# untitled.net
KiCad netlist of a schematic drawn in EAGLE
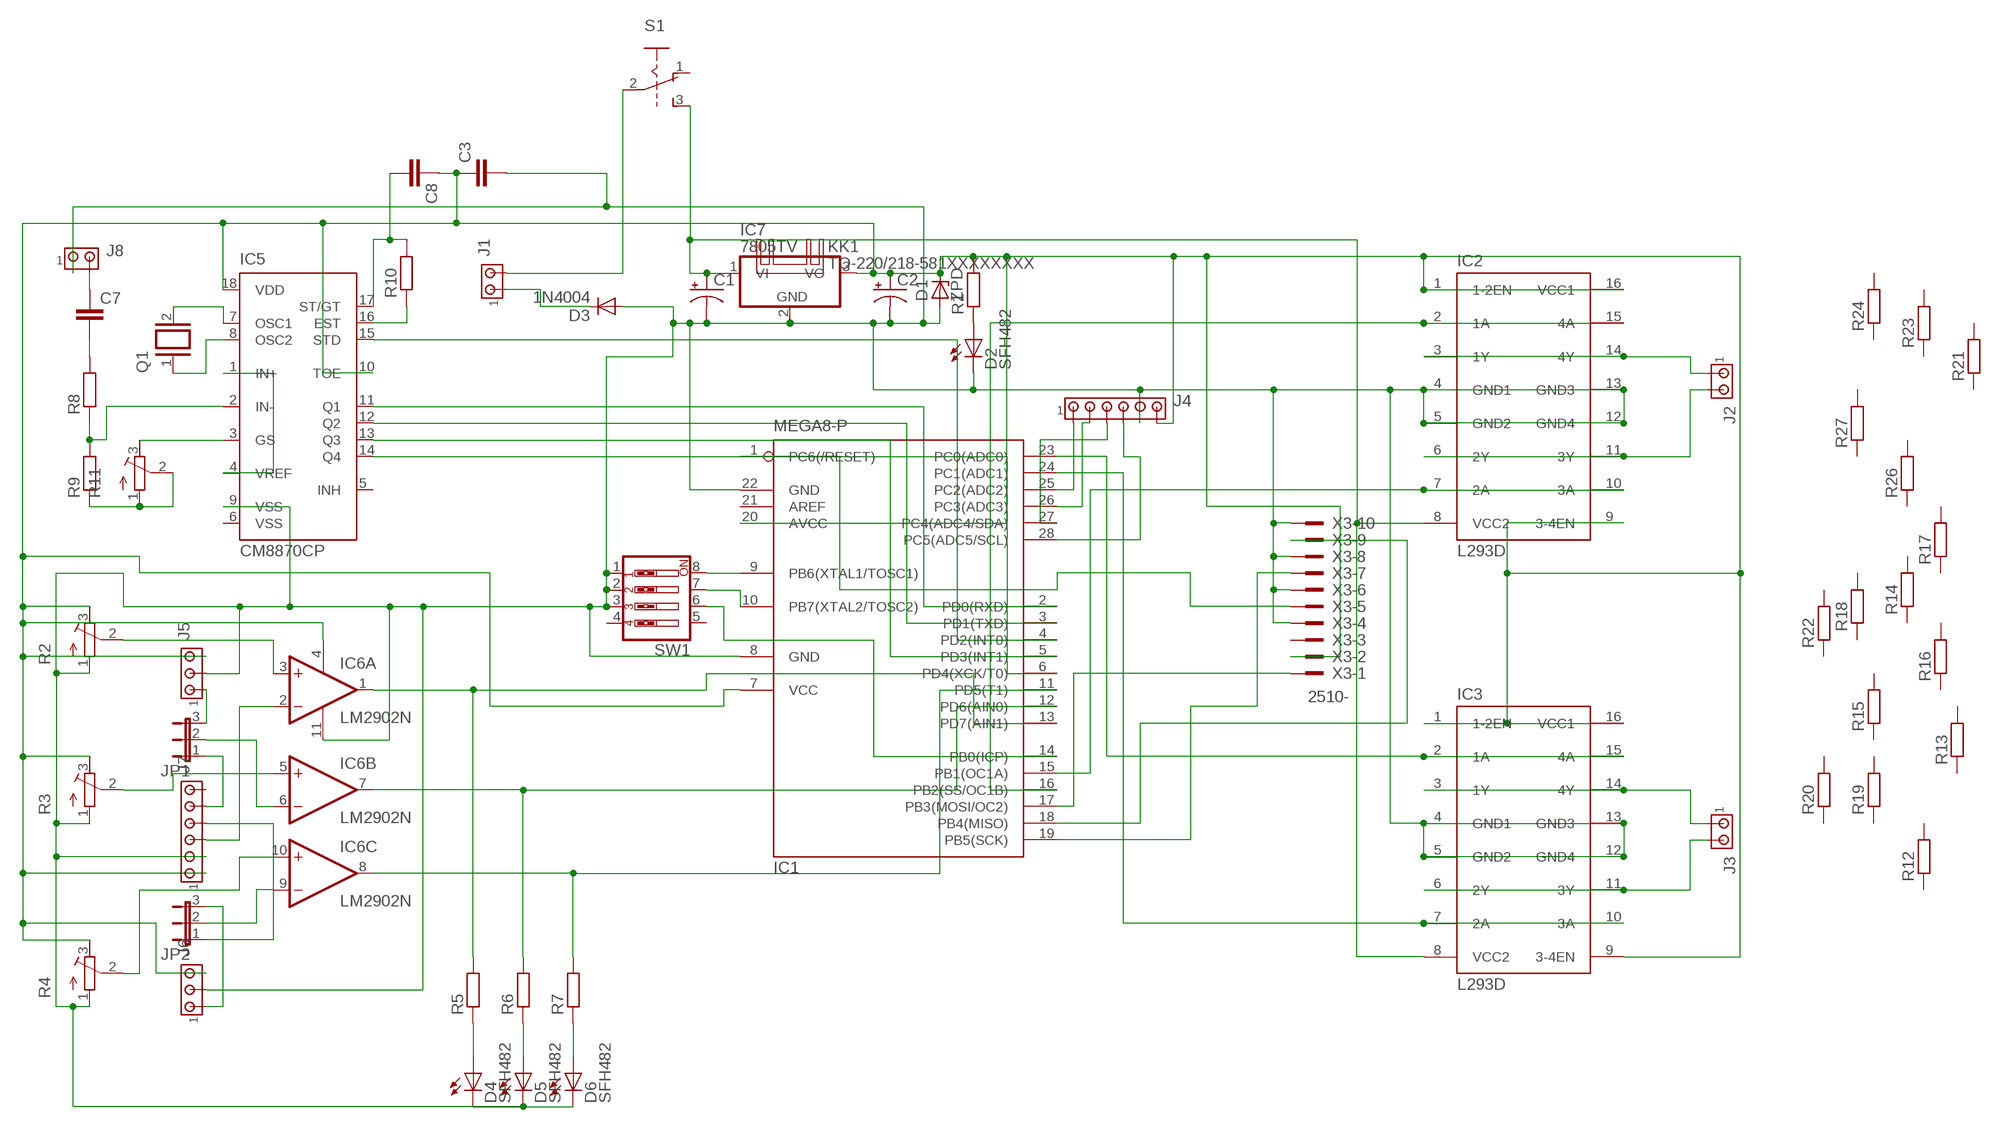
[diagram p0: schematic, sheet 1]

(export (version "E")
  (design (tool "Eeschema 10.0.6"))
  (components
    (comp (ref "C1")
      (value "CPOL-USE5-10.5")
      (footprint "eagle-import:E5-10,5")
      (libsource (lib "eagle-import") (part "CPOL-USE5-10.5"))
    )
    (comp (ref "C2")
      (value "CPOL-USE5-10.5")
      (footprint "eagle-import:E5-10,5")
      (libsource (lib "eagle-import") (part "CPOL-USE5-10.5"))
    )
    (comp (ref "C3")
      (value "C2.5/2")
      (footprint "eagle-import:C2.5-2")
      (libsource (lib "eagle-import") (part "C2.5/2"))
    )
    (comp (ref "C7")
      (value "C5/2.5")
      (footprint "eagle-import:C5B2.5")
      (libsource (lib "eagle-import") (part "C5/2.5"))
    )
    (comp (ref "C8")
      (value "C5/2.5")
      (footprint "eagle-import:C5B2.5")
      (libsource (lib "eagle-import") (part "C5/2.5"))
    )
    (comp (ref "D1")
      (value "ZPD")
      (footprint "eagle-import:DO35Z10")
      (libsource (lib "eagle-import") (part "ZPD"))
    )
    (comp (ref "D2")
      (value "SFH482")
      (footprint "eagle-import:SFH482")
      (libsource (lib "eagle-import") (part "SFH482"))
    )
    (comp (ref "D3")
      (value "1N4004")
      (footprint "eagle-import:DO41-10")
      (libsource (lib "eagle-import") (part "1N4004"))
    )
    (comp (ref "D4")
      (value "SFH482")
      (footprint "eagle-import:SFH482")
      (libsource (lib "eagle-import") (part "SFH482"))
    )
    (comp (ref "D5")
      (value "SFH482")
      (footprint "eagle-import:SFH482")
      (libsource (lib "eagle-import") (part "SFH482"))
    )
    (comp (ref "D6")
      (value "SFH482")
      (footprint "eagle-import:SFH482")
      (libsource (lib "eagle-import") (part "SFH482"))
    )
    (comp (ref "IC1")
      (value "MEGA8-P")
      (footprint "eagle-import:DIL28-3")
      (libsource (lib "eagle-import") (part "MEGA8-P"))
    )
    (comp (ref "IC2")
      (value "L293D")
      (footprint "eagle-import:DIL16")
      (libsource (lib "eagle-import") (part "L293D"))
    )
    (comp (ref "IC3")
      (value "L293D")
      (footprint "eagle-import:DIL16")
      (libsource (lib "eagle-import") (part "L293D"))
    )
    (comp (ref "IC5")
      (value "CM8870CP")
      (footprint "eagle-import:DIL18")
      (libsource (lib "eagle-import") (part "CM8870CP"))
    )
    (comp (ref "IC6")
      (value "LM2902N")
      (footprint "eagle-import:DIL14")
      (libsource (lib "eagle-import") (part "LM2902N"))
    )
    (comp (ref "IC7")
      (value "7805TV")
      (footprint "eagle-import:TO220V")
      (libsource (lib "eagle-import") (part "78TV05"))
    )
    (comp (ref "J1")
      (value "MTA02-100")
      (footprint "eagle-import:10X02MTA")
      (libsource (lib "eagle-import") (part "MTA02-100"))
    )
    (comp (ref "J2")
      (value "MTA02-156")
      (footprint "eagle-import:1X2MTA")
      (libsource (lib "eagle-import") (part "MTA02-156"))
    )
    (comp (ref "J3")
      (value "MTA02-156")
      (footprint "eagle-import:1X2MTA")
      (libsource (lib "eagle-import") (part "MTA02-156"))
    )
    (comp (ref "J4")
      (value "MTA06-100")
      (footprint "eagle-import:10X06MTA")
      (libsource (lib "eagle-import") (part "MTA06-100"))
    )
    (comp (ref "J5")
      (value "MTA03-100")
      (footprint "eagle-import:10X03MTA")
      (libsource (lib "eagle-import") (part "MTA03-100"))
    )
    (comp (ref "J6")
      (value "MTA03-100")
      (footprint "eagle-import:10X03MTA")
      (libsource (lib "eagle-import") (part "MTA03-100"))
    )
    (comp (ref "J7")
      (value "MTA06-100")
      (footprint "eagle-import:10X06MTA")
      (libsource (lib "eagle-import") (part "MTA06-100"))
    )
    (comp (ref "J8")
      (value "MTA02-100")
      (footprint "eagle-import:10X02MTA")
      (libsource (lib "eagle-import") (part "MTA02-100"))
    )
    (comp (ref "JP1")
      (value "JP2E")
      (footprint "eagle-import:JP2")
      (libsource (lib "eagle-import") (part "JP2E"))
    )
    (comp (ref "JP2")
      (value "JP2E")
      (footprint "eagle-import:JP2")
      (libsource (lib "eagle-import") (part "JP2E"))
    )
    (comp (ref "KK1")
      (value "TO-220/218-581XXXXXXXX")
      (footprint "eagle-import:581XXXXXXXX")
      (libsource (lib "eagle-import") (part "TO-220/218-581XXXXXXXX"))
    )
    (comp (ref "Q1")
      (value "XTAL/S")
      (footprint "eagle-import:QS")
      (libsource (lib "eagle-import") (part "XTAL/S"))
    )
    (comp (ref "R1")
      (value "R-EU_0207/10")
      (footprint "eagle-import:0207_10")
      (libsource (lib "eagle-import") (part "resistor_R-EU_0207/10"))
    )
    (comp (ref "R2")
      (value "R-TRIMM3296W")
      (footprint "eagle-import:RTRIM3296W")
      (libsource (lib "eagle-import") (part "R-TRIMM3296W"))
    )
    (comp (ref "R3")
      (value "R-TRIMM3296W")
      (footprint "eagle-import:RTRIM3296W")
      (libsource (lib "eagle-import") (part "R-TRIMM3296W"))
    )
    (comp (ref "R4")
      (value "R-TRIMM3296W")
      (footprint "eagle-import:RTRIM3296W")
      (libsource (lib "eagle-import") (part "R-TRIMM3296W"))
    )
    (comp (ref "R5")
      (value "R-EU_0207/10")
      (footprint "eagle-import:0207_10")
      (libsource (lib "eagle-import") (part "resistor_R-EU_0207/10"))
    )
    (comp (ref "R6")
      (value "R-EU_0207/10")
      (footprint "eagle-import:0207_10")
      (libsource (lib "eagle-import") (part "resistor_R-EU_0207/10"))
    )
    (comp (ref "R7")
      (value "R-EU_0207/10")
      (footprint "eagle-import:0207_10")
      (libsource (lib "eagle-import") (part "resistor_R-EU_0207/10"))
    )
    (comp (ref "R8")
      (value "R-EU_0207/10")
      (footprint "eagle-import:0207_10")
      (libsource (lib "eagle-import") (part "R-EU_0207/10"))
    )
    (comp (ref "R9")
      (value "R-EU_0207/10")
      (footprint "eagle-import:0207_10")
      (libsource (lib "eagle-import") (part "R-EU_0207/10"))
    )
    (comp (ref "R10")
      (value "R-EU_0207/10")
      (footprint "eagle-import:0207_10")
      (libsource (lib "eagle-import") (part "R-EU_0207/10"))
    )
    (comp (ref "R11")
      (value "R-TRIMM3296W")
      (footprint "eagle-import:RTRIM3296W")
      (libsource (lib "eagle-import") (part "R-TRIMM3296W"))
    )
    (comp (ref "R12")
      (value "R-EU_0207/10")
      (footprint "eagle-import:0207_10")
      (libsource (lib "eagle-import") (part "R-EU_0207/10"))
    )
    (comp (ref "R13")
      (value "R-EU_0204/7")
      (footprint "eagle-import:0204_7")
      (libsource (lib "eagle-import") (part "R-EU_0204/7"))
    )
    (comp (ref "R14")
      (value "R-EU_0204/7")
      (footprint "eagle-import:0204_7")
      (libsource (lib "eagle-import") (part "R-EU_0204/7"))
    )
    (comp (ref "R15")
      (value "R-EU_0204/7")
      (footprint "eagle-import:0204_7")
      (libsource (lib "eagle-import") (part "R-EU_0204/7"))
    )
    (comp (ref "R16")
      (value "R-EU_0204/7")
      (footprint "eagle-import:0204_7")
      (libsource (lib "eagle-import") (part "R-EU_0204/7"))
    )
    (comp (ref "R17")
      (value "R-EU_0204/7")
      (footprint "eagle-import:0204_7")
      (libsource (lib "eagle-import") (part "R-EU_0204/7"))
    )
    (comp (ref "R18")
      (value "R-EU_0204/7")
      (footprint "eagle-import:0204_7")
      (libsource (lib "eagle-import") (part "R-EU_0204/7"))
    )
    (comp (ref "R19")
      (value "R-EU_0204/7")
      (footprint "eagle-import:0204_7")
      (libsource (lib "eagle-import") (part "R-EU_0204/7"))
    )
    (comp (ref "R20")
      (value "R-EU_0204/7")
      (footprint "eagle-import:0204_7")
      (libsource (lib "eagle-import") (part "R-EU_0204/7"))
    )
    (comp (ref "R21")
      (value "R-EU_0207/12")
      (footprint "eagle-import:0207_12")
      (libsource (lib "eagle-import") (part "R-EU_0207/12"))
    )
    (comp (ref "R22")
      (value "R-EU_0204/7")
      (footprint "eagle-import:0204_7")
      (libsource (lib "eagle-import") (part "R-EU_0204/7"))
    )
    (comp (ref "R23")
      (value "R-EU_0207/12")
      (footprint "eagle-import:0207_12")
      (libsource (lib "eagle-import") (part "R-EU_0207/12"))
    )
    (comp (ref "R24")
      (value "R-EU_0207/12")
      (footprint "eagle-import:0207_12")
      (libsource (lib "eagle-import") (part "R-EU_0207/12"))
    )
    (comp (ref "R26")
      (value "R-EU_0204/7")
      (footprint "eagle-import:0204_7")
      (libsource (lib "eagle-import") (part "R-EU_0204/7"))
    )
    (comp (ref "R27")
      (value "R-EU_0204/7")
      (footprint "eagle-import:0204_7")
      (libsource (lib "eagle-import") (part "R-EU_0204/7"))
    )
    (comp (ref "S1")
      (value "A68-A31")
      (footprint "eagle-import:A68-A31")
      (libsource (lib "eagle-import") (part "A68-A31"))
    )
    (comp (ref "SW1")
      (value "SW_DIP-4")
      (footprint "eagle-import:EDG-04")
      (libsource (lib "eagle-import") (part "SW_DIP-4"))
    )
    (comp (ref "X3")
      (value "2510-")
      (footprint "eagle-import:PAK100_2500-10")
      (libsource (lib "eagle-import") (part "2510-"))
    )
  )
  (nets
    (net (code "1") (name "/VSS") (class "Default")
      (node (ref "IC5") (pin "6") (pinfunction "VSS_6") (pintype "power_in"))
    )
    (net (code "2") (name "Net-(C7-Pad1)") (class "Default")
      (node (ref "C7") (pin "1") (pinfunction "1_1") (pintype "passive"))
      (node (ref "J8") (pin "2") (pinfunction "2_2") (pintype "passive"))
    )
    (net (code "3") (name "Net-(C7-Pad2)") (class "Default")
      (node (ref "C7") (pin "2") (pinfunction "2_2") (pintype "passive"))
      (node (ref "R8") (pin "2") (pinfunction "2_2") (pintype "passive"))
    )
    (net (code "4") (name "Net-(D2-C)") (class "Default")
      (node (ref "C1") (pin "-") (pinfunction "-_-") (pintype "passive"))
      (node (ref "C2") (pin "-") (pinfunction "-_-") (pintype "passive"))
      (node (ref "C3") (pin "2") (pinfunction "2_2") (pintype "passive"))
      (node (ref "D1") (pin "A") (pinfunction "A_A") (pintype "passive"))
      (node (ref "D2") (pin "K") (pinfunction "C_K") (pintype "passive"))
      (node (ref "D3") (pin "A") (pinfunction "A_A") (pintype "passive"))
      (node (ref "D4") (pin "K") (pinfunction "C_K") (pintype "passive"))
      (node (ref "D5") (pin "K") (pinfunction "C_K") (pintype "passive"))
      (node (ref "D6") (pin "K") (pinfunction "C_K") (pintype "passive"))
      (node (ref "IC1") (pin "22") (pinfunction "GND_22") (pintype "power_in"))
      (node (ref "IC1") (pin "8") (pinfunction "GND_8") (pintype "power_in"))
      (node (ref "IC2") (pin "12") (pinfunction "GND4_12") (pintype "power_in"))
      (node (ref "IC2") (pin "13") (pinfunction "GND3_13") (pintype "power_in"))
      (node (ref "IC2") (pin "4") (pinfunction "GND1_4") (pintype "power_in"))
      (node (ref "IC2") (pin "5") (pinfunction "GND2_5") (pintype "power_in"))
      (node (ref "IC3") (pin "12") (pinfunction "GND4_12") (pintype "power_in"))
      (node (ref "IC3") (pin "13") (pinfunction "GND3_13") (pintype "power_in"))
      (node (ref "IC3") (pin "4") (pinfunction "GND1_4") (pintype "power_in"))
      (node (ref "IC3") (pin "5") (pinfunction "GND2_5") (pintype "power_in"))
      (node (ref "IC5") (pin "9") (pinfunction "VSS_9") (pintype "power_in"))
      (node (ref "IC6") (pin "11") (pinfunction "V-_11") (pintype "power_in"))
      (node (ref "IC7") (pin "2") (pinfunction "GND_2") (pintype "passive"))
      (node (ref "J4") (pin "2") (pinfunction "5_2") (pintype "passive"))
      (node (ref "J5") (pin "2") (pinfunction "2_2") (pintype "passive"))
      (node (ref "J6") (pin "2") (pinfunction "2_2") (pintype "passive"))
      (node (ref "J7") (pin "5") (pinfunction "2_5") (pintype "passive"))
      (node (ref "J8") (pin "1") (pinfunction "1_1") (pintype "passive"))
      (node (ref "R2") (pin "1") (pinfunction "E_1") (pintype "passive"))
      (node (ref "R3") (pin "1") (pinfunction "E_1") (pintype "passive"))
      (node (ref "R4") (pin "1") (pinfunction "E_1") (pintype "passive"))
      (node (ref "SW1") (pin "1") (pinfunction "1_1") (pintype "passive"))
      (node (ref "SW1") (pin "2") (pinfunction "2_2") (pintype "passive"))
      (node (ref "SW1") (pin "3") (pinfunction "3_3") (pintype "passive"))
      (node (ref "X3") (pin "10") (pinfunction "KL_10") (pintype "passive"))
      (node (ref "X3") (pin "4") (pinfunction "KL_4") (pintype "passive"))
      (node (ref "X3") (pin "6") (pinfunction "KL_6") (pintype "passive"))
      (node (ref "X3") (pin "8") (pinfunction "KL_8") (pintype "passive"))
    )
    (net (code "5") (name "Net-(D2-PadA)") (class "Default")
      (node (ref "D2") (pin "A") (pinfunction "A_A") (pintype "passive"))
      (node (ref "R1") (pin "1") (pinfunction "1_1") (pintype "passive"))
    )
    (net (code "6") (name "Net-(D3-PadC)") (class "Default")
      (node (ref "D3") (pin "C") (pinfunction "C_C") (pintype "passive"))
      (node (ref "J1") (pin "1") (pinfunction "1_1") (pintype "passive"))
    )
    (net (code "7") (name "Net-(D4-PadA)") (class "Default")
      (node (ref "D4") (pin "A") (pinfunction "A_A") (pintype "passive"))
      (node (ref "R5") (pin "1") (pinfunction "1_1") (pintype "passive"))
    )
    (net (code "8") (name "Net-(D5-PadA)") (class "Default")
      (node (ref "D5") (pin "A") (pinfunction "A_A") (pintype "passive"))
      (node (ref "R6") (pin "1") (pinfunction "1_1") (pintype "passive"))
    )
    (net (code "9") (name "Net-(D6-PadA)") (class "Default")
      (node (ref "D6") (pin "A") (pinfunction "A_A") (pintype "passive"))
      (node (ref "R7") (pin "1") (pinfunction "1_1") (pintype "passive"))
    )
    (net (code "10") (name "Net-(IC1-AVCC)") (class "Default")
      (node (ref "C2") (pin "+") (pinfunction "+_+") (pintype "passive"))
      (node (ref "C3") (pin "1") (pinfunction "1_1") (pintype "passive"))
      (node (ref "C8") (pin "1") (pinfunction "1_1") (pintype "passive"))
      (node (ref "D1") (pin "C") (pinfunction "C_C") (pintype "passive"))
      (node (ref "IC1") (pin "20") (pinfunction "AVCC_20") (pintype "power_in"))
      (node (ref "IC1") (pin "7") (pinfunction "VCC_7") (pintype "power_in"))
      (node (ref "IC2") (pin "1") (pinfunction "1-2EN_1") (pintype "input"))
      (node (ref "IC2") (pin "16") (pinfunction "VCC1_16") (pintype "power_in"))
      (node (ref "IC2") (pin "9") (pinfunction "3-4EN_9") (pintype "input"))
      (node (ref "IC3") (pin "1") (pinfunction "1-2EN_1") (pintype "input"))
      (node (ref "IC3") (pin "16") (pinfunction "VCC1_16") (pintype "power_in"))
      (node (ref "IC3") (pin "9") (pinfunction "3-4EN_9") (pintype "input"))
      (node (ref "IC5") (pin "10") (pinfunction "TOE_10") (pintype "input"))
      (node (ref "IC5") (pin "18") (pinfunction "VDD_18") (pintype "power_in"))
      (node (ref "IC6") (pin "4") (pinfunction "V+_4") (pintype "power_in"))
      (node (ref "IC7") (pin "3") (pinfunction "VO_3") (pintype "passive"))
      (node (ref "J4") (pin "1") (pinfunction "6_1") (pintype "passive"))
      (node (ref "J5") (pin "3") (pinfunction "3_3") (pintype "passive"))
      (node (ref "J6") (pin "3") (pinfunction "3_3") (pintype "passive"))
      (node (ref "J7") (pin "6") (pinfunction "1_6") (pintype "passive"))
      (node (ref "R1") (pin "2") (pinfunction "2_2") (pintype "passive"))
      (node (ref "R2") (pin "3") (pinfunction "A_3") (pintype "passive"))
      (node (ref "R3") (pin "3") (pinfunction "A_3") (pintype "passive"))
      (node (ref "R4") (pin "3") (pinfunction "A_3") (pintype "passive"))
      (node (ref "X3") (pin "2") (pinfunction "KL_2") (pintype "passive"))
    )
    (net (code "11") (name "Net-(IC1-PB0(ICP))") (class "Default")
      (node (ref "IC1") (pin "14") (pinfunction "PB0(ICP)_14") (pintype "bidirectional"))
      (node (ref "SW1") (pin "6") (pinfunction "6_6") (pintype "passive"))
    )
    (net (code "12") (name "Net-(IC1-PB1(OC1A))") (class "Default")
      (node (ref "IC1") (pin "15") (pinfunction "PB1(OC1A)_15") (pintype "bidirectional"))
      (node (ref "IC2") (pin "10") (pinfunction "3A_10") (pintype "input"))
      (node (ref "IC2") (pin "7") (pinfunction "2A_7") (pintype "input"))
    )
    (net (code "13") (name "Net-(IC1-PB2(SS{slash}OC1B))") (class "Default")
      (node (ref "IC1") (pin "16") (pinfunction "PB2(SS/OC1B)_16") (pintype "bidirectional"))
      (node (ref "IC2") (pin "15") (pinfunction "4A_15") (pintype "input"))
      (node (ref "IC2") (pin "2") (pinfunction "1A_2") (pintype "input"))
    )
    (net (code "14") (name "Net-(IC1-PB3(MOSI{slash}OC2))") (class "Default")
      (node (ref "IC1") (pin "17") (pinfunction "PB3(MOSI/OC2)_17") (pintype "bidirectional"))
      (node (ref "X3") (pin "1") (pinfunction "KL_1") (pintype "passive"))
    )
    (net (code "15") (name "Net-(IC1-PB4(MISO))") (class "Default")
      (node (ref "IC1") (pin "18") (pinfunction "PB4(MISO)_18") (pintype "bidirectional"))
      (node (ref "X3") (pin "9") (pinfunction "KL_9") (pintype "passive"))
    )
    (net (code "16") (name "Net-(IC1-PB5(SCK))") (class "Default")
      (node (ref "IC1") (pin "19") (pinfunction "PB5(SCK)_19") (pintype "bidirectional"))
      (node (ref "X3") (pin "7") (pinfunction "KL_7") (pintype "passive"))
    )
    (net (code "17") (name "Net-(IC1-PB6(XTAL1{slash}TOSC1))") (class "Default")
      (node (ref "IC1") (pin "9") (pinfunction "PB6(XTAL1/TOSC1)_9") (pintype "bidirectional"))
      (node (ref "SW1") (pin "8") (pinfunction "8_8") (pintype "passive"))
    )
    (net (code "18") (name "Net-(IC1-PB7(XTAL2{slash}TOSC2))") (class "Default")
      (node (ref "IC1") (pin "10") (pinfunction "PB7(XTAL2/TOSC2)_10") (pintype "bidirectional"))
      (node (ref "SW1") (pin "7") (pinfunction "7_7") (pintype "passive"))
    )
    (net (code "19") (name "Net-(IC1-PC0(ADC0))") (class "Default")
      (node (ref "IC1") (pin "23") (pinfunction "PC0(ADC0)_23") (pintype "bidirectional"))
      (node (ref "IC3") (pin "15") (pinfunction "4A_15") (pintype "input"))
      (node (ref "IC3") (pin "2") (pinfunction "1A_2") (pintype "input"))
    )
    (net (code "20") (name "Net-(IC1-PC1(ADC1))") (class "Default")
      (node (ref "IC1") (pin "24") (pinfunction "PC1(ADC1)_24") (pintype "bidirectional"))
      (node (ref "IC3") (pin "10") (pinfunction "3A_10") (pintype "input"))
      (node (ref "IC3") (pin "7") (pinfunction "2A_7") (pintype "input"))
    )
    (net (code "21") (name "Net-(IC1-PC2(ADC2))") (class "Default")
      (node (ref "IC1") (pin "25") (pinfunction "PC2(ADC2)_25") (pintype "bidirectional"))
      (node (ref "J4") (pin "6") (pinfunction "1_6") (pintype "passive"))
    )
    (net (code "22") (name "Net-(IC1-PC3(ADC3))") (class "Default")
      (node (ref "IC1") (pin "26") (pinfunction "PC3(ADC3)_26") (pintype "bidirectional"))
      (node (ref "J4") (pin "5") (pinfunction "2_5") (pintype "passive"))
    )
    (net (code "23") (name "Net-(IC1-PC4(ADC4{slash}SDA))") (class "Default")
      (node (ref "IC1") (pin "27") (pinfunction "PC4(ADC4/SDA)_27") (pintype "bidirectional"))
      (node (ref "J4") (pin "4") (pinfunction "3_4") (pintype "passive"))
    )
    (net (code "24") (name "Net-(IC1-PC5(ADC5{slash}SCL))") (class "Default")
      (node (ref "IC1") (pin "28") (pinfunction "PC5(ADC5/SCL)_28") (pintype "bidirectional"))
      (node (ref "J4") (pin "3") (pinfunction "4_3") (pintype "passive"))
    )
    (net (code "25") (name "Net-(IC1-PC6({slash}RESET))") (class "Default")
      (node (ref "IC1") (pin "1") (pinfunction "PC6(/RESET)_1") (pintype "bidirectional"))
      (node (ref "X3") (pin "5") (pinfunction "KL_5") (pintype "passive"))
    )
    (net (code "26") (name "Net-(IC1-PD0(RXD))") (class "Default")
      (node (ref "IC1") (pin "2") (pinfunction "PD0(RXD)_2") (pintype "bidirectional"))
      (node (ref "IC5") (pin "11") (pinfunction "Q1_11") (pintype "output"))
    )
    (net (code "27") (name "Net-(IC1-PD1(TXD))") (class "Default")
      (node (ref "IC1") (pin "3") (pinfunction "PD1(TXD)_3") (pintype "bidirectional"))
      (node (ref "IC5") (pin "12") (pinfunction "Q2_12") (pintype "output"))
    )
    (net (code "28") (name "Net-(IC1-PD2(INT0))") (class "Default")
      (node (ref "IC1") (pin "4") (pinfunction "PD2(INT0)_4") (pintype "bidirectional"))
      (node (ref "IC5") (pin "15") (pinfunction "STD_15") (pintype "input"))
    )
    (net (code "29") (name "Net-(IC1-PD3(INT1))") (class "Default")
      (node (ref "IC1") (pin "5") (pinfunction "PD3(INT1)_5") (pintype "bidirectional"))
      (node (ref "IC5") (pin "13") (pinfunction "Q3_13") (pintype "output"))
    )
    (net (code "30") (name "Net-(IC1-PD4(XCK{slash}T0))") (class "Default")
      (node (ref "IC1") (pin "6") (pinfunction "PD4(XCK/T0)_6") (pintype "bidirectional"))
      (node (ref "IC5") (pin "14") (pinfunction "Q4_14") (pintype "output"))
    )
    (net (code "31") (name "Net-(IC1-PD5(T1))") (class "Default")
      (node (ref "IC1") (pin "11") (pinfunction "PD5(T1)_11") (pintype "bidirectional"))
      (node (ref "IC6") (pin "8") (pinfunction "OUT_8") (pintype "output"))
      (node (ref "R7") (pin "2") (pinfunction "2_2") (pintype "passive"))
    )
    (net (code "32") (name "Net-(IC1-PD6(AIN0))") (class "Default")
      (node (ref "IC1") (pin "12") (pinfunction "PD6(AIN0)_12") (pintype "bidirectional"))
      (node (ref "IC6") (pin "7") (pinfunction "OUT_7") (pintype "output"))
      (node (ref "R6") (pin "2") (pinfunction "2_2") (pintype "passive"))
    )
    (net (code "33") (name "Net-(IC1-PD7(AIN1))") (class "Default")
      (node (ref "IC1") (pin "13") (pinfunction "PD7(AIN1)_13") (pintype "bidirectional"))
      (node (ref "IC6") (pin "1") (pinfunction "OUT_1") (pintype "output"))
      (node (ref "R5") (pin "2") (pinfunction "2_2") (pintype "passive"))
    )
    (net (code "34") (name "Net-(IC2-1Y)") (class "Default")
      (node (ref "IC2") (pin "14") (pinfunction "4Y_14") (pintype "output"))
      (node (ref "IC2") (pin "3") (pinfunction "1Y_3") (pintype "output"))
      (node (ref "J2") (pin "1") (pinfunction "1_1") (pintype "passive"))
    )
    (net (code "35") (name "Net-(IC2-2Y)") (class "Default")
      (node (ref "IC2") (pin "11") (pinfunction "3Y_11") (pintype "output"))
      (node (ref "IC2") (pin "6") (pinfunction "2Y_6") (pintype "output"))
      (node (ref "J2") (pin "2") (pinfunction "2_2") (pintype "passive"))
    )
    (net (code "36") (name "Net-(IC2-VCC2)") (class "Default")
      (node (ref "C1") (pin "+") (pinfunction "+_+") (pintype "passive"))
      (node (ref "IC2") (pin "8") (pinfunction "VCC2_8") (pintype "power_in"))
      (node (ref "IC3") (pin "8") (pinfunction "VCC2_8") (pintype "power_in"))
      (node (ref "IC7") (pin "1") (pinfunction "VI_1") (pintype "input"))
      (node (ref "S1") (pin "3") (pinfunction "S_3") (pintype "passive"))
    )
    (net (code "37") (name "Net-(IC3-1Y)") (class "Default")
      (node (ref "IC3") (pin "14") (pinfunction "4Y_14") (pintype "output"))
      (node (ref "IC3") (pin "3") (pinfunction "1Y_3") (pintype "output"))
      (node (ref "J3") (pin "1") (pinfunction "1_1") (pintype "passive"))
    )
    (net (code "38") (name "Net-(IC3-2Y)") (class "Default")
      (node (ref "IC3") (pin "11") (pinfunction "3Y_11") (pintype "output"))
      (node (ref "IC3") (pin "6") (pinfunction "2Y_6") (pintype "output"))
      (node (ref "J3") (pin "2") (pinfunction "2_2") (pintype "passive"))
    )
    (net (code "39") (name "Net-(IC5-EST)") (class "Default")
      (node (ref "IC5") (pin "16") (pinfunction "EST_16") (pintype "input"))
      (node (ref "R10") (pin "1") (pinfunction "1_1") (pintype "passive"))
    )
    (net (code "40") (name "Net-(IC5-GS)") (class "Default")
      (node (ref "IC5") (pin "3") (pinfunction "GS_3") (pintype "input"))
      (node (ref "R11") (pin "3") (pinfunction "A_3") (pintype "passive"))
    )
    (net (code "41") (name "Net-(IC5-IN+)") (class "Default")
      (node (ref "IC5") (pin "1") (pinfunction "IN+_1") (pintype "input"))
      (node (ref "IC5") (pin "4") (pinfunction "VREF_4") (pintype "output"))
    )
    (net (code "42") (name "Net-(IC5-IN-)") (class "Default")
      (node (ref "IC5") (pin "2") (pinfunction "IN-_2") (pintype "input"))
      (node (ref "R8") (pin "1") (pinfunction "1_1") (pintype "passive"))
      (node (ref "R9") (pin "2") (pinfunction "2_2") (pintype "passive"))
    )
    (net (code "43") (name "Net-(IC5-OSC1)") (class "Default")
      (node (ref "IC5") (pin "7") (pinfunction "OSC1_7") (pintype "input"))
      (node (ref "Q1") (pin "2") (pinfunction "2_2") (pintype "passive"))
    )
    (net (code "44") (name "Net-(IC5-OSC2)") (class "Default")
      (node (ref "IC5") (pin "8") (pinfunction "OSC2_8") (pintype "bidirectional"))
      (node (ref "Q1") (pin "1") (pinfunction "1_1") (pintype "passive"))
    )
    (net (code "45") (name "Net-(IC5-ST{slash}GT)") (class "Default")
      (node (ref "C8") (pin "2") (pinfunction "2_2") (pintype "passive"))
      (node (ref "IC5") (pin "17") (pinfunction "ST/GT_17") (pintype "bidirectional"))
      (node (ref "R10") (pin "2") (pinfunction "2_2") (pintype "passive"))
    )
    (net (code "46") (name "Net-(IC6A-+IN)") (class "Default")
      (node (ref "IC6") (pin "3") (pinfunction "+IN_3") (pintype "input"))
      (node (ref "R2") (pin "2") (pinfunction "S_2") (pintype "passive"))
    )
    (net (code "47") (name "Net-(IC6A--IN)") (class "Default")
      (node (ref "IC6") (pin "2") (pinfunction "-IN_2") (pintype "input"))
      (node (ref "J7") (pin "4") (pinfunction "3_4") (pintype "passive"))
    )
    (net (code "48") (name "Net-(IC6B-+IN)") (class "Default")
      (node (ref "IC6") (pin "5") (pinfunction "+IN_5") (pintype "input"))
      (node (ref "R3") (pin "2") (pinfunction "S_2") (pintype "passive"))
    )
    (net (code "49") (name "Net-(IC6B--IN)") (class "Default")
      (node (ref "IC6") (pin "6") (pinfunction "-IN_6") (pintype "input"))
      (node (ref "JP1") (pin "2") (pinfunction "2_2") (pintype "passive"))
    )
    (net (code "50") (name "Net-(IC6C-+IN)") (class "Default")
      (node (ref "IC6") (pin "10") (pinfunction "+IN_10") (pintype "input"))
      (node (ref "R4") (pin "2") (pinfunction "S_2") (pintype "passive"))
    )
    (net (code "51") (name "Net-(IC6C--IN)") (class "Default")
      (node (ref "IC6") (pin "9") (pinfunction "-IN_9") (pintype "input"))
      (node (ref "JP2") (pin "2") (pinfunction "2_2") (pintype "passive"))
    )
    (net (code "52") (name "Net-(J5-Pad1)") (class "Default")
      (node (ref "J5") (pin "1") (pinfunction "1_1") (pintype "passive"))
      (node (ref "JP1") (pin "3") (pinfunction "3_3") (pintype "passive"))
    )
    (net (code "53") (name "Net-(J6-Pad1)") (class "Default")
      (node (ref "J6") (pin "1") (pinfunction "1_1") (pintype "passive"))
      (node (ref "JP2") (pin "3") (pinfunction "3_3") (pintype "passive"))
    )
    (net (code "54") (name "Net-(J7-4)") (class "Default")
      (node (ref "J7") (pin "3") (pinfunction "4_3") (pintype "passive"))
      (node (ref "JP2") (pin "1") (pinfunction "1_1") (pintype "passive"))
    )
    (net (code "55") (name "Net-(J7-5)") (class "Default")
      (node (ref "J7") (pin "2") (pinfunction "5_2") (pintype "passive"))
      (node (ref "JP1") (pin "1") (pinfunction "1_1") (pintype "passive"))
    )
    (net (code "56") (name "Net-(R11-E)") (class "Default")
      (node (ref "R11") (pin "1") (pinfunction "E_1") (pintype "passive"))
      (node (ref "R11") (pin "2") (pinfunction "S_2") (pintype "passive"))
      (node (ref "R9") (pin "1") (pinfunction "1_1") (pintype "passive"))
    )
    (net (code "57") (name "Net-(S1A-P)") (class "Default")
      (node (ref "J1") (pin "2") (pinfunction "2_2") (pintype "passive"))
      (node (ref "S1") (pin "2") (pinfunction "P_2") (pintype "passive"))
    )
    (net (code "58") (name "unconnected-(IC1-AREF-Pad21)") (class "Default")
      (node (ref "IC1") (pin "21") (pinfunction "AREF_21") (pintype "passive"))
    )
    (net (code "59") (name "unconnected-(IC5-INH-Pad5)") (class "Default")
      (node (ref "IC5") (pin "5") (pinfunction "INH_5") (pintype "input"))
    )
    (net (code "60") (name "unconnected-(J7-6-Pad1)") (class "Default")
      (node (ref "J7") (pin "1") (pinfunction "6_1") (pintype "passive"))
    )
    (net (code "61") (name "unconnected-(R12-Pad1)") (class "Default")
      (node (ref "R12") (pin "1") (pinfunction "1_1") (pintype "passive"))
    )
    (net (code "62") (name "unconnected-(R12-Pad2)") (class "Default")
      (node (ref "R12") (pin "2") (pinfunction "2_2") (pintype "passive"))
    )
    (net (code "63") (name "unconnected-(R13-Pad1)") (class "Default")
      (node (ref "R13") (pin "1") (pinfunction "1_1") (pintype "passive"))
    )
    (net (code "64") (name "unconnected-(R13-Pad2)") (class "Default")
      (node (ref "R13") (pin "2") (pinfunction "2_2") (pintype "passive"))
    )
    (net (code "65") (name "unconnected-(R14-Pad1)") (class "Default")
      (node (ref "R14") (pin "1") (pinfunction "1_1") (pintype "passive"))
    )
    (net (code "66") (name "unconnected-(R14-Pad2)") (class "Default")
      (node (ref "R14") (pin "2") (pinfunction "2_2") (pintype "passive"))
    )
    (net (code "67") (name "unconnected-(R15-Pad1)") (class "Default")
      (node (ref "R15") (pin "1") (pinfunction "1_1") (pintype "passive"))
    )
    (net (code "68") (name "unconnected-(R15-Pad2)") (class "Default")
      (node (ref "R15") (pin "2") (pinfunction "2_2") (pintype "passive"))
    )
    (net (code "69") (name "unconnected-(R16-Pad1)") (class "Default")
      (node (ref "R16") (pin "1") (pinfunction "1_1") (pintype "passive"))
    )
    (net (code "70") (name "unconnected-(R16-Pad2)") (class "Default")
      (node (ref "R16") (pin "2") (pinfunction "2_2") (pintype "passive"))
    )
    (net (code "71") (name "unconnected-(R17-Pad1)") (class "Default")
      (node (ref "R17") (pin "1") (pinfunction "1_1") (pintype "passive"))
    )
    (net (code "72") (name "unconnected-(R17-Pad2)") (class "Default")
      (node (ref "R17") (pin "2") (pinfunction "2_2") (pintype "passive"))
    )
    (net (code "73") (name "unconnected-(R18-Pad1)") (class "Default")
      (node (ref "R18") (pin "1") (pinfunction "1_1") (pintype "passive"))
    )
    (net (code "74") (name "unconnected-(R18-Pad2)") (class "Default")
      (node (ref "R18") (pin "2") (pinfunction "2_2") (pintype "passive"))
    )
    (net (code "75") (name "unconnected-(R19-Pad1)") (class "Default")
      (node (ref "R19") (pin "1") (pinfunction "1_1") (pintype "passive"))
    )
    (net (code "76") (name "unconnected-(R19-Pad2)") (class "Default")
      (node (ref "R19") (pin "2") (pinfunction "2_2") (pintype "passive"))
    )
    (net (code "77") (name "unconnected-(R20-Pad1)") (class "Default")
      (node (ref "R20") (pin "1") (pinfunction "1_1") (pintype "passive"))
    )
    (net (code "78") (name "unconnected-(R20-Pad2)") (class "Default")
      (node (ref "R20") (pin "2") (pinfunction "2_2") (pintype "passive"))
    )
    (net (code "79") (name "unconnected-(R21-Pad1)") (class "Default")
      (node (ref "R21") (pin "1") (pinfunction "1_1") (pintype "passive"))
    )
    (net (code "80") (name "unconnected-(R21-Pad2)") (class "Default")
      (node (ref "R21") (pin "2") (pinfunction "2_2") (pintype "passive"))
    )
    (net (code "81") (name "unconnected-(R22-Pad1)") (class "Default")
      (node (ref "R22") (pin "1") (pinfunction "1_1") (pintype "passive"))
    )
    (net (code "82") (name "unconnected-(R22-Pad2)") (class "Default")
      (node (ref "R22") (pin "2") (pinfunction "2_2") (pintype "passive"))
    )
    (net (code "83") (name "unconnected-(R23-Pad1)") (class "Default")
      (node (ref "R23") (pin "1") (pinfunction "1_1") (pintype "passive"))
    )
    (net (code "84") (name "unconnected-(R23-Pad2)") (class "Default")
      (node (ref "R23") (pin "2") (pinfunction "2_2") (pintype "passive"))
    )
    (net (code "85") (name "unconnected-(R24-Pad1)") (class "Default")
      (node (ref "R24") (pin "1") (pinfunction "1_1") (pintype "passive"))
    )
    (net (code "86") (name "unconnected-(R24-Pad2)") (class "Default")
      (node (ref "R24") (pin "2") (pinfunction "2_2") (pintype "passive"))
    )
    (net (code "87") (name "unconnected-(R26-Pad1)") (class "Default")
      (node (ref "R26") (pin "1") (pinfunction "1_1") (pintype "passive"))
    )
    (net (code "88") (name "unconnected-(R26-Pad2)") (class "Default")
      (node (ref "R26") (pin "2") (pinfunction "2_2") (pintype "passive"))
    )
    (net (code "89") (name "unconnected-(R27-Pad1)") (class "Default")
      (node (ref "R27") (pin "1") (pinfunction "1_1") (pintype "passive"))
    )
    (net (code "90") (name "unconnected-(R27-Pad2)") (class "Default")
      (node (ref "R27") (pin "2") (pinfunction "2_2") (pintype "passive"))
    )
    (net (code "91") (name "unconnected-(S1A-O-Pad1)") (class "Default")
      (node (ref "S1") (pin "1") (pinfunction "O_1") (pintype "passive"))
    )
    (net (code "92") (name "unconnected-(SW1-Pad4)") (class "Default")
      (node (ref "SW1") (pin "4") (pinfunction "4_4") (pintype "passive"))
    )
    (net (code "93") (name "unconnected-(SW1-Pad5)") (class "Default")
      (node (ref "SW1") (pin "5") (pinfunction "5_5") (pintype "passive"))
    )
    (net (code "94") (name "unconnected-(X3D-KL-Pad3)") (class "Default")
      (node (ref "X3") (pin "3") (pinfunction "KL_3") (pintype "passive"))
    )
  )
)
